# Filter_Capacitors_-_Port_L.net
KiCad netlist of a schematic drawn in Altium Designer
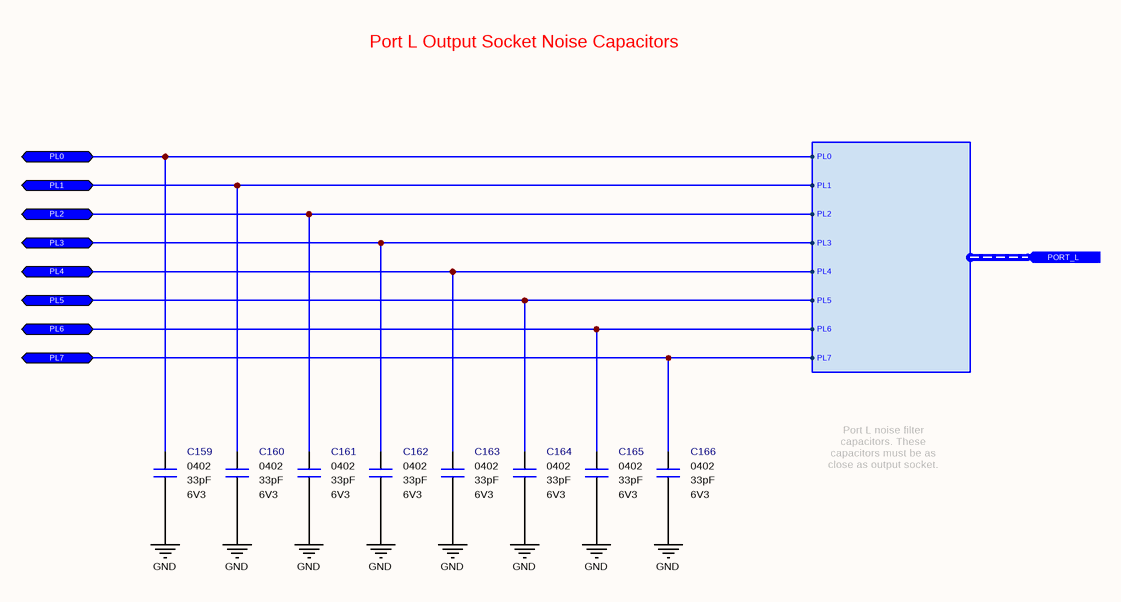
[diagram p0: Filter Capacitors - Port L.SchDoc]

(export (version "E")
  (design (tool "Eeschema 10.0.6"))
  (components
    (comp (ref "C159")
      (value "33pF")
      (footprint "CAPACITOR_0402")
      (description "Capacitor - 33pF [0402] (Ceramic)")
      (fields
        (field (name "TOLERANCE") "10%")
        (field (name "CASE") "0402")
        (field (name "VOLTAGE") "6V3")
        (field (name "MANUFACTURER PART NUMBER") "C0402C330J9RACAUTO")
      )
      (libsource (lib "Ovoo_Library") (part "Capacitor - 33pF [0402-6V3]"))
    )
    (comp (ref "C160")
      (value "33pF")
      (footprint "CAPACITOR_0402")
      (description "Capacitor - 33pF [0402] (Ceramic)")
      (fields
        (field (name "TOLERANCE") "10%")
        (field (name "CASE") "0402")
        (field (name "VOLTAGE") "6V3")
        (field (name "MANUFACTURER PART NUMBER") "C0402C330J9RACAUTO")
      )
      (libsource (lib "Ovoo_Library") (part "Capacitor - 33pF [0402-6V3]"))
    )
    (comp (ref "C161")
      (value "33pF")
      (footprint "CAPACITOR_0402")
      (description "Capacitor - 33pF [0402] (Ceramic)")
      (fields
        (field (name "TOLERANCE") "10%")
        (field (name "CASE") "0402")
        (field (name "VOLTAGE") "6V3")
        (field (name "MANUFACTURER PART NUMBER") "C0402C330J9RACAUTO")
      )
      (libsource (lib "Ovoo_Library") (part "Capacitor - 33pF [0402-6V3]"))
    )
    (comp (ref "C162")
      (value "33pF")
      (footprint "CAPACITOR_0402")
      (description "Capacitor - 33pF [0402] (Ceramic)")
      (fields
        (field (name "TOLERANCE") "10%")
        (field (name "CASE") "0402")
        (field (name "VOLTAGE") "6V3")
        (field (name "MANUFACTURER PART NUMBER") "C0402C330J9RACAUTO")
      )
      (libsource (lib "Ovoo_Library") (part "Capacitor - 33pF [0402-6V3]"))
    )
    (comp (ref "C163")
      (value "33pF")
      (footprint "CAPACITOR_0402")
      (description "Capacitor - 33pF [0402] (Ceramic)")
      (fields
        (field (name "TOLERANCE") "10%")
        (field (name "CASE") "0402")
        (field (name "VOLTAGE") "6V3")
        (field (name "MANUFACTURER PART NUMBER") "C0402C330J9RACAUTO")
      )
      (libsource (lib "Ovoo_Library") (part "Capacitor - 33pF [0402-6V3]"))
    )
    (comp (ref "C164")
      (value "33pF")
      (footprint "CAPACITOR_0402")
      (description "Capacitor - 33pF [0402] (Ceramic)")
      (fields
        (field (name "TOLERANCE") "10%")
        (field (name "CASE") "0402")
        (field (name "VOLTAGE") "6V3")
        (field (name "MANUFACTURER PART NUMBER") "C0402C330J9RACAUTO")
      )
      (libsource (lib "Ovoo_Library") (part "Capacitor - 33pF [0402-6V3]"))
    )
    (comp (ref "C165")
      (value "33pF")
      (footprint "CAPACITOR_0402")
      (description "Capacitor - 33pF [0402] (Ceramic)")
      (fields
        (field (name "TOLERANCE") "10%")
        (field (name "CASE") "0402")
        (field (name "VOLTAGE") "6V3")
        (field (name "MANUFACTURER PART NUMBER") "C0402C330J9RACAUTO")
      )
      (libsource (lib "Ovoo_Library") (part "Capacitor - 33pF [0402-6V3]"))
    )
    (comp (ref "C166")
      (value "33pF")
      (footprint "CAPACITOR_0402")
      (description "Capacitor - 33pF [0402] (Ceramic)")
      (fields
        (field (name "TOLERANCE") "10%")
        (field (name "CASE") "0402")
        (field (name "VOLTAGE") "6V3")
        (field (name "MANUFACTURER PART NUMBER") "C0402C330J9RACAUTO")
      )
      (libsource (lib "Ovoo_Library") (part "Capacitor - 33pF [0402-6V3]"))
    )
  )
  (nets
    (net (code "2") (name "/PL0") (class "Default")
      (node (ref "C159") (pin "2") (pinfunction "2_2") (pintype "passive"))
    )
    (net (code "3") (name "/PL1") (class "Default")
      (node (ref "C160") (pin "2") (pinfunction "2_2") (pintype "passive"))
    )
    (net (code "4") (name "/PL2") (class "Default")
      (node (ref "C161") (pin "2") (pinfunction "2_2") (pintype "passive"))
    )
    (net (code "5") (name "/PL3") (class "Default")
      (node (ref "C162") (pin "2") (pinfunction "2_2") (pintype "passive"))
    )
    (net (code "6") (name "/PL4") (class "Default")
      (node (ref "C163") (pin "2") (pinfunction "2_2") (pintype "passive"))
    )
    (net (code "7") (name "/PL5") (class "Default")
      (node (ref "C164") (pin "2") (pinfunction "2_2") (pintype "passive"))
    )
    (net (code "8") (name "/PL6") (class "Default")
      (node (ref "C165") (pin "2") (pinfunction "2_2") (pintype "passive"))
    )
    (net (code "9") (name "/PL7") (class "Default")
      (node (ref "C166") (pin "2") (pinfunction "2_2") (pintype "passive"))
    )
    (net (code "11") (name "GND") (class "Default")
      (node (ref "C159") (pin "1") (pinfunction "1_1") (pintype "passive"))
      (node (ref "C160") (pin "1") (pinfunction "1_1") (pintype "passive"))
      (node (ref "C161") (pin "1") (pinfunction "1_1") (pintype "passive"))
      (node (ref "C162") (pin "1") (pinfunction "1_1") (pintype "passive"))
      (node (ref "C163") (pin "1") (pinfunction "1_1") (pintype "passive"))
      (node (ref "C164") (pin "1") (pinfunction "1_1") (pintype "passive"))
      (node (ref "C165") (pin "1") (pinfunction "1_1") (pintype "passive"))
      (node (ref "C166") (pin "1") (pinfunction "1_1") (pintype "passive"))
    )
  )
)
